# BMS_Interface.net
KiCad netlist of a schematic drawn in Altium Designer
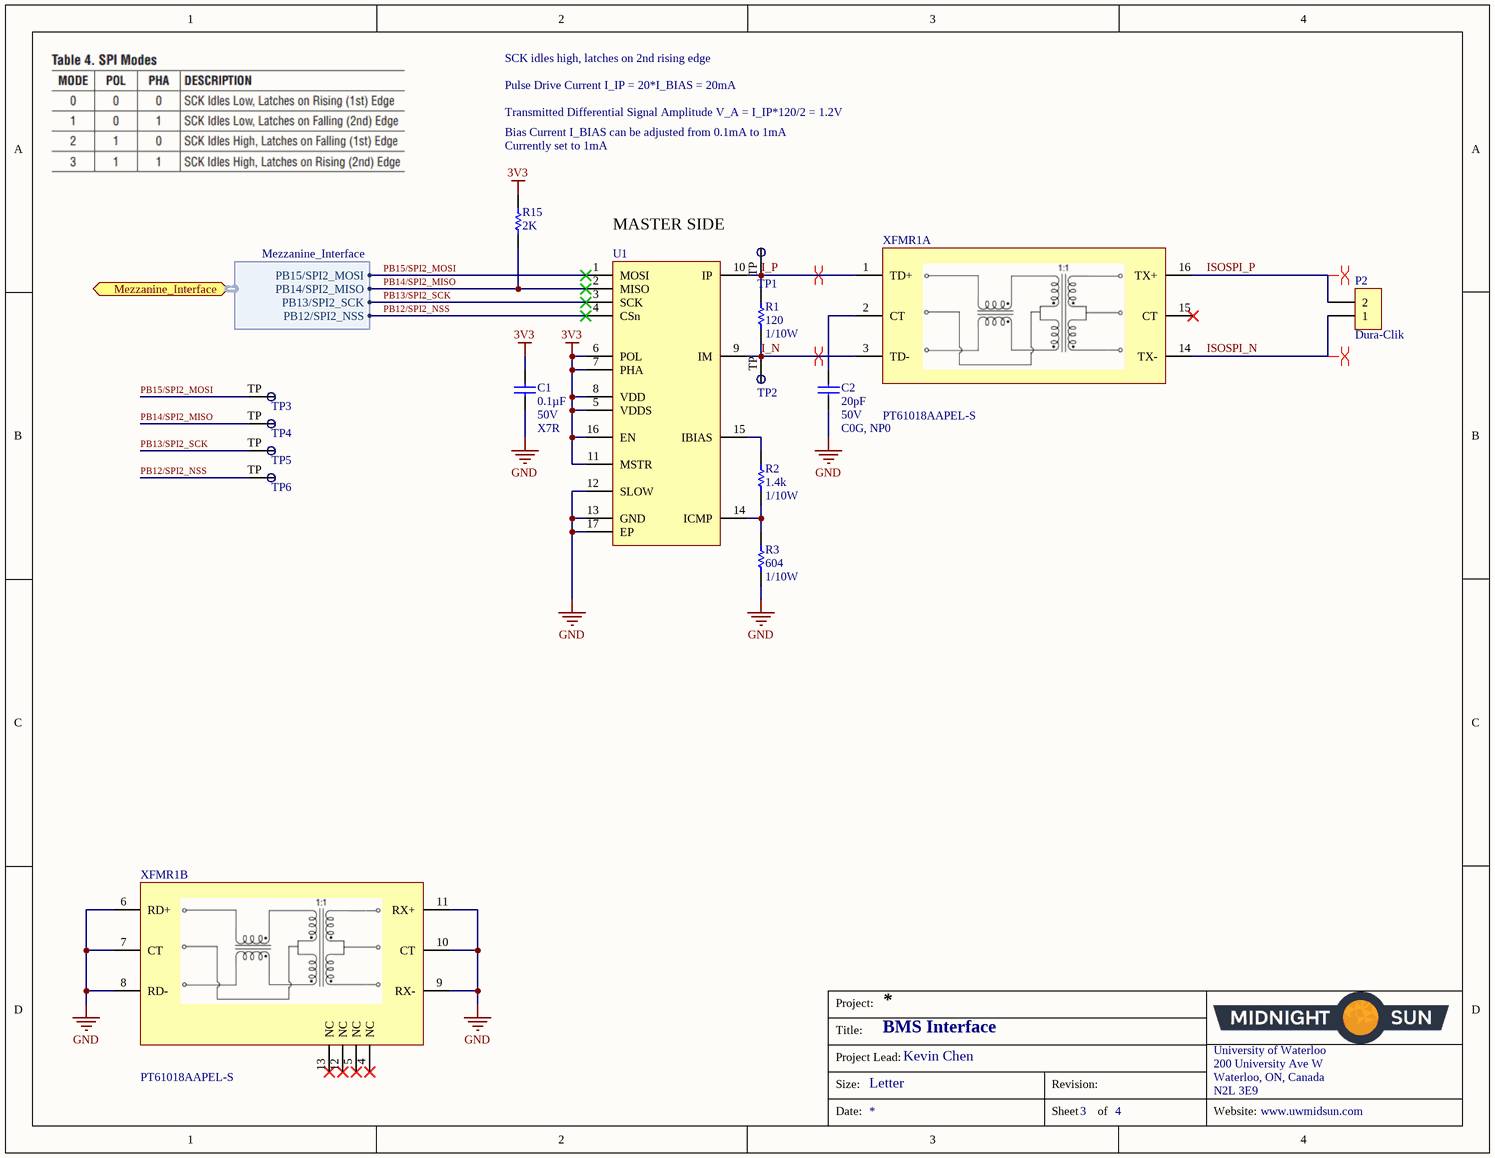
[diagram p0: BMS_Interface.SchDoc]

(export (version "E")
  (design (tool "Eeschema 10.0.6"))
  (components
    (comp (ref "C1")
      (value "CAP CER 0.1UF 50V 10% X7R 0603")
      (footprint "CAP, 0603")
      (description "0.10µF ±10% 50V Ceramic Capacitor X7R 0603 (1608 Metric)")
      (fields
        (field (name "TOLERANCE") "±10%")
        (field (name "CAPACITANCE") "0.1µF")
        (field (name "VOLTAGE") "50V")
        (field (name "TEMPERATURE COEFFICIENT") "X7R")
      )
      (libsource (lib "Schematic Diagrams") (part "CAP CER 0.1UF 50V 10% X7R 0603"))
    )
    (comp (ref "C2")
      (value "CAP CER 20PF 50V ±5% C0G/NP0 0603")
      (footprint "CAP, 0603")
      (description "20pF ±5% 50V Ceramic Capacitor C0G, NP0 0603 (1608 Metric)")
      (fields
        (field (name "TOLERANCE") "±5%")
        (field (name "CAPACITANCE") "20pF")
        (field (name "VOLTAGE") "50V")
        (field (name "TEMPERATURE COEFFICIENT") "C0G, NP0")
      )
      (libsource (lib "Schematic Diagrams") (part "CAP CER 20PF 50V ±5% C0G/NP0 0603"))
    )
    (comp (ref "P2")
      (value "Dura-Clik")
      (footprint "CONN, 2POS Dura-Click Vertical")
      (description "2 Positions Header, Shrouded Connector 0.079\" (2.00mm) Surface Mount, Vertical Tin")
      (fields
        (field (name "MANUFACTURER") "Molex, LLC")
        (field (name "MANUFACTURER PART NUMBER") "5600200220")
      )
      (libsource (lib "Schematic Diagrams") (part "CONN 2POS DURA-CLIK 0.079{dblquote} VERT"))
    )
    (comp (ref "R1")
      (value "RES 120 OHM 1% 1/10W 0603")
      (footprint "RES, 0603")
      (description "RES SMD 120 OHM 1% 1/10W 0603")
      (fields
        (field (name "TOLERANCE") "±1%")
        (field (name "RESISTANCE") "120")
        (field (name "POWER") "1/10W")
      )
      (libsource (lib "Schematic Diagrams") (part "RES 120 OHM 1% 1/10W 0603"))
    )
    (comp (ref "R2")
      (value "RES 1.4k OHM 1% 1/10W 0603")
      (footprint "RES, 0603")
      (description "RES SMD 1.4K OHM 1% 1/10W 0603")
      (fields
        (field (name "TOLERANCE") "±1%")
        (field (name "RESISTANCE") "1.4k")
        (field (name "POWER") "1/10W")
      )
      (libsource (lib "Schematic Diagrams") (part "RES 1.4k OHM 1% 1/10W 0603"))
    )
    (comp (ref "R3")
      (value "RES 604 OHM 1% 1/10W 0603")
      (footprint "RES, 0603")
      (description "RES SMD 604 OHM 1% 1/10W 0603")
      (fields
        (field (name "TOLERANCE") "±1%")
        (field (name "RESISTANCE") "604")
        (field (name "POWER") "1/10W")
      )
      (libsource (lib "Schematic Diagrams") (part "RES 604 OHM 1% 1/10W 0603"))
    )
    (comp (ref "R15")
      (value "2K")
      (footprint "RES, 0603")
      (description "2k Ohm ±1% 0.1W, 1/10W Chip Resistor 0603 (1608 Metric) Moisture Resistant Thick Film")
      (fields
        (field (name "MANUFACTURER") "Yageo")
        (field (name "MANUFACTURER PART NUMBER") "RC0603FR-072KL")
      )
      (libsource (lib "Schematic Diagrams") (part "RES 2K OHM 1% 1/10W 0603"))
    )
    (comp (ref "TP1")
      (value "Test Point")
      (footprint "Test Point")
      (libsource (lib "Schematic Diagrams") (part "Test Point"))
    )
    (comp (ref "TP2")
      (value "Test Point")
      (footprint "Test Point")
      (libsource (lib "Schematic Diagrams") (part "Test Point"))
    )
    (comp (ref "TP3")
      (value "Test Point")
      (footprint "Test Point")
      (libsource (lib "Schematic Diagrams") (part "Test Point"))
    )
    (comp (ref "TP4")
      (value "Test Point")
      (footprint "Test Point")
      (libsource (lib "Schematic Diagrams") (part "Test Point"))
    )
    (comp (ref "TP5")
      (value "Test Point")
      (footprint "Test Point")
      (libsource (lib "Schematic Diagrams") (part "Test Point"))
    )
    (comp (ref "TP6")
      (value "Test Point")
      (footprint "Test Point")
      (libsource (lib "Schematic Diagrams") (part "Test Point"))
    )
    (comp (ref "U1")
      (value "IC ISOSPI COMM INTERFACE LTC6820IUD")
      (footprint "IC COMM INTERFACE ISOSPI 16-QFN")
      (description "IC COMM INTERFACE ISOSPI 16-QFN")
      (fields
        (field (name "MANUFACTURER") "Linear Technology")
        (field (name "MANUFACTURER PART NUMBER") "LTC6820IUD#PBF")
      )
      (libsource (lib "Schematic Diagrams") (part "IC ISOSPI COMM INTERFACE LTC6820IUD"))
    )
    (comp (ref "XFMR1")
      (value "IC PULSE XFMR 1CT:1CT 350UH SMD")
      (footprint "IC, PULSE XFMR 1CT:1CT 350UH SMD")
      (description "PULSE XFMR 1CT:1CT 350UH SMD")
      (fields (field (name "MANUFACTURER") "Bourns Inc.") (field (name "MFG_PN") "PT61018AAPEL-S"))
      (libsource (lib "Schematic Diagrams") (part "IC PULSE XFMR 1CT{colon}1CT 350UH SMD"))
    )
  )
  (nets
    (net (code "2") (name "/ISOSPI_N") (class "Default")
      (node (ref "P2") (pin "1") (pinfunction "1_1") (pintype "passive"))
      (node (ref "XFMR1") (pin "14") (pinfunction "TX-_14") (pintype "passive"))
    )
    (net (code "3") (name "/ISOSPI_P") (class "Default")
      (node (ref "P2") (pin "2") (pinfunction "2_2") (pintype "passive"))
      (node (ref "XFMR1") (pin "16") (pinfunction "TX+_16") (pintype "passive"))
    )
    (net (code "4") (name "/I_N") (class "Default")
      (node (ref "R1") (pin "2") (pinfunction "2_2") (pintype "passive"))
      (node (ref "TP2") (pin "TP") (pinfunction "1_TP") (pintype "passive"))
      (node (ref "U1") (pin "9") (pinfunction "IM_9") (pintype "passive"))
      (node (ref "XFMR1") (pin "3") (pinfunction "TD-_3") (pintype "passive"))
    )
    (net (code "5") (name "/I_P") (class "Default")
      (node (ref "R1") (pin "1") (pinfunction "1_1") (pintype "passive"))
      (node (ref "TP1") (pin "TP") (pinfunction "1_TP") (pintype "passive"))
      (node (ref "U1") (pin "10") (pinfunction "IP_10") (pintype "passive"))
      (node (ref "XFMR1") (pin "1") (pinfunction "TD+_1") (pintype "passive"))
    )
    (net (code "6") (name "/PB12{slash}SPI2_NSS") (class "Default")
      (node (ref "TP6") (pin "TP") (pinfunction "1_TP") (pintype "passive"))
      (node (ref "U1") (pin "4") (pinfunction "CSn_4") (pintype "passive"))
    )
    (net (code "7") (name "/PB13{slash}SPI2_SCK") (class "Default")
      (node (ref "TP5") (pin "TP") (pinfunction "1_TP") (pintype "passive"))
      (node (ref "U1") (pin "3") (pinfunction "SCK_3") (pintype "passive"))
    )
    (net (code "8") (name "/PB14{slash}SPI2_MISO") (class "Default")
      (node (ref "R15") (pin "2") (pinfunction "2_2") (pintype "passive"))
      (node (ref "TP4") (pin "TP") (pinfunction "1_TP") (pintype "passive"))
      (node (ref "U1") (pin "2") (pinfunction "MISO_2") (pintype "passive"))
    )
    (net (code "9") (name "/PB15{slash}SPI2_MOSI") (class "Default")
      (node (ref "TP3") (pin "TP") (pinfunction "1_TP") (pintype "passive"))
      (node (ref "U1") (pin "1") (pinfunction "MOSI_1") (pintype "passive"))
    )
    (net (code "11") (name "3V3") (class "Default")
      (node (ref "C1") (pin "1") (pinfunction "1_1") (pintype "passive"))
      (node (ref "R15") (pin "1") (pinfunction "1_1") (pintype "passive"))
      (node (ref "U1") (pin "11") (pinfunction "MSTR_11") (pintype "passive"))
      (node (ref "U1") (pin "16") (pinfunction "EN_16") (pintype "passive"))
      (node (ref "U1") (pin "5") (pinfunction "VDDS_5") (pintype "passive"))
      (node (ref "U1") (pin "6") (pinfunction "POL_6") (pintype "passive"))
      (node (ref "U1") (pin "7") (pinfunction "PHA_7") (pintype "passive"))
      (node (ref "U1") (pin "8") (pinfunction "VDD_8") (pintype "passive"))
    )
    (net (code "12") (name "GND") (class "Default")
      (node (ref "C1") (pin "2") (pinfunction "2_2") (pintype "passive"))
      (node (ref "C2") (pin "2") (pinfunction "2_2") (pintype "passive"))
      (node (ref "R3") (pin "2") (pinfunction "2_2") (pintype "passive"))
      (node (ref "U1") (pin "12") (pinfunction "SLOW_12") (pintype "passive"))
      (node (ref "U1") (pin "13") (pinfunction "GND_13") (pintype "passive"))
      (node (ref "U1") (pin "17") (pinfunction "EP_17") (pintype "passive"))
      (node (ref "XFMR1") (pin "10") (pinfunction "CT_10") (pintype "passive"))
      (node (ref "XFMR1") (pin "11") (pinfunction "RX+_11") (pintype "passive"))
      (node (ref "XFMR1") (pin "6") (pinfunction "RD+_6") (pintype "passive"))
      (node (ref "XFMR1") (pin "7") (pinfunction "CT_7") (pintype "passive"))
      (node (ref "XFMR1") (pin "8") (pinfunction "RD-_8") (pintype "passive"))
      (node (ref "XFMR1") (pin "9") (pinfunction "RX-_9") (pintype "passive"))
    )
    (net (code "13") (name "Net-(C2-Pad1)") (class "Default")
      (node (ref "C2") (pin "1") (pinfunction "1_1") (pintype "passive"))
      (node (ref "XFMR1") (pin "2") (pinfunction "CT_2") (pintype "passive"))
    )
    (net (code "14") (name "Net-(U1-IBIAS)") (class "Default")
      (node (ref "R2") (pin "1") (pinfunction "1_1") (pintype "passive"))
      (node (ref "U1") (pin "15") (pinfunction "IBIAS_15") (pintype "passive"))
    )
    (net (code "15") (name "Net-(U1-ICMP)") (class "Default")
      (node (ref "R2") (pin "2") (pinfunction "2_2") (pintype "passive"))
      (node (ref "R3") (pin "1") (pinfunction "1_1") (pintype "passive"))
      (node (ref "U1") (pin "14") (pinfunction "ICMP_14") (pintype "passive"))
    )
    (net (code "16") (name "unconnected-(XFMR1A-CT-Pad15)") (class "Default")
      (node (ref "XFMR1") (pin "15") (pinfunction "CT_15") (pintype "passive+no_connect"))
    )
    (net (code "17") (name "unconnected-(XFMR1B-NC-Pad4)") (class "Default")
      (node (ref "XFMR1") (pin "4") (pinfunction "NC_4") (pintype "passive+no_connect"))
    )
    (net (code "18") (name "unconnected-(XFMR1B-NC-Pad5)") (class "Default")
      (node (ref "XFMR1") (pin "5") (pinfunction "NC_5") (pintype "passive+no_connect"))
    )
    (net (code "19") (name "unconnected-(XFMR1B-NC-Pad12)") (class "Default")
      (node (ref "XFMR1") (pin "12") (pinfunction "NC_12") (pintype "passive+no_connect"))
    )
    (net (code "20") (name "unconnected-(XFMR1B-NC-Pad13)") (class "Default")
      (node (ref "XFMR1") (pin "13") (pinfunction "NC_13") (pintype "passive+no_connect"))
    )
  )
)
